# HW2.net
KiCad netlist of a schematic drawn in EAGLE
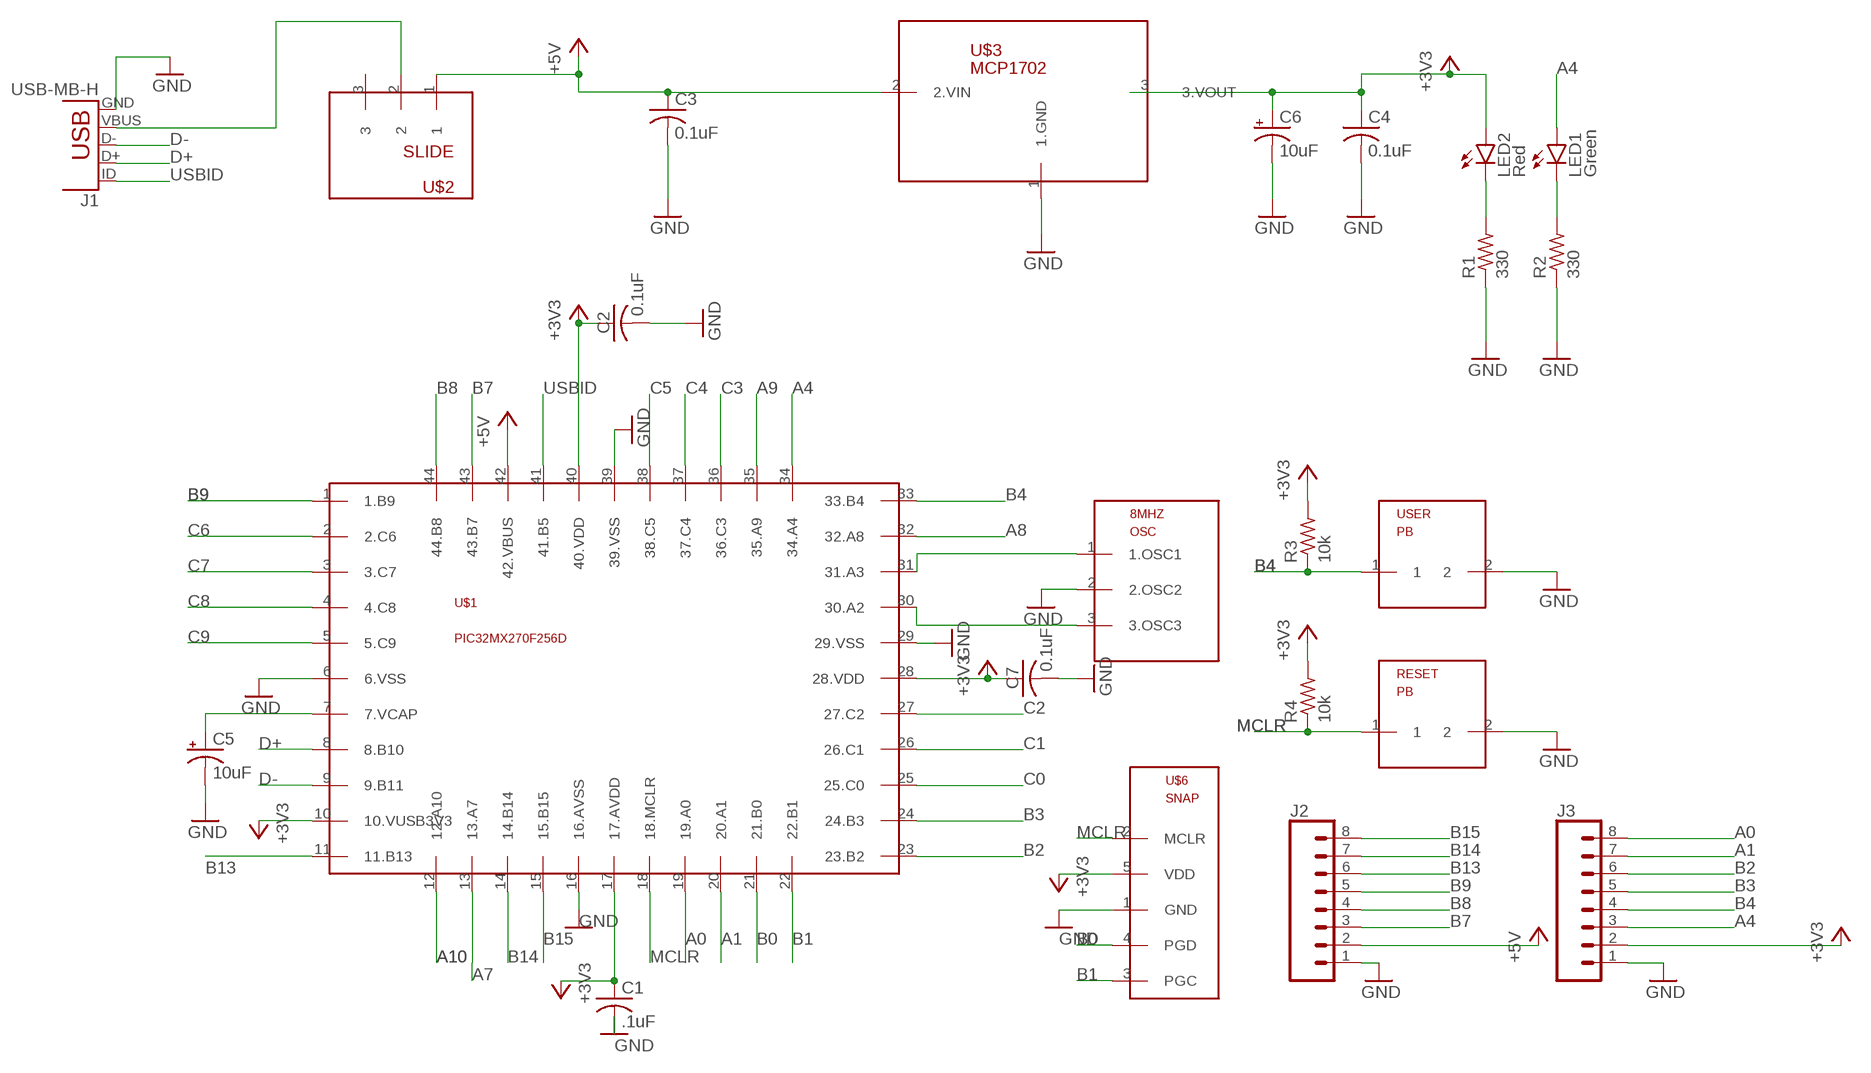
[diagram p0: schematic, sheet 1]

(export (version "E")
  (design (tool "Eeschema 10.0.6"))
  (components
    (comp (ref "8MHZ")
      (value "OSC")
      (footprint "eagle-import:OSC")
      (libsource (lib "eagle-import") (part "OSC"))
    )
    (comp (ref "C1")
      (value ".1uF")
      (footprint "eagle-import:C025-025X050")
      (libsource (lib "eagle-import") (part "C-US025-025X050"))
    )
    (comp (ref "C2")
      (value "0.1uF")
      (footprint "eagle-import:C025-025X050")
      (libsource (lib "eagle-import") (part "C-US025-025X050"))
    )
    (comp (ref "C3")
      (value "0.1uF")
      (footprint "eagle-import:C025-025X050")
      (libsource (lib "eagle-import") (part "C-US025-025X050"))
    )
    (comp (ref "C4")
      (value "0.1uF")
      (footprint "eagle-import:C025-025X050")
      (libsource (lib "eagle-import") (part "C-US025-025X050"))
    )
    (comp (ref "C5")
      (value "10uF")
      (footprint "eagle-import:B45181B")
      (libsource (lib "eagle-import") (part "CPOL-USB45181B"))
    )
    (comp (ref "C6")
      (value "10uF")
      (footprint "eagle-import:B45181B")
      (libsource (lib "eagle-import") (part "CPOL-USB45181B"))
    )
    (comp (ref "C7")
      (value "0.1uF")
      (footprint "eagle-import:C025-025X050")
      (libsource (lib "eagle-import") (part "C-US025-025X050"))
    )
    (comp (ref "J1")
      (value "USB-MB-H")
      (footprint "eagle-import:USB-MB-H")
      (libsource (lib "eagle-import") (part "USB-MB-H"))
    )
    (comp (ref "J2")
      (value "CONN_08")
      (footprint "eagle-import:CONN_08")
      (libsource (lib "eagle-import") (part "CONN_08"))
    )
    (comp (ref "J3")
      (value "CONN_08")
      (footprint "eagle-import:CONN_08")
      (libsource (lib "eagle-import") (part "CONN_08"))
    )
    (comp (ref "LED1")
      (value "Green")
      (footprint "eagle-import:LED3MM")
      (libsource (lib "eagle-import") (part "LED3MM"))
    )
    (comp (ref "LED2")
      (value "Red")
      (footprint "eagle-import:LED3MM")
      (libsource (lib "eagle-import") (part "LED3MM"))
    )
    (comp (ref "R1")
      (value "330")
      (footprint "eagle-import:0207_10")
      (libsource (lib "eagle-import") (part "R-US_0207/10"))
    )
    (comp (ref "R2")
      (value "330")
      (footprint "eagle-import:0207_10")
      (libsource (lib "eagle-import") (part "R-US_0207/10"))
    )
    (comp (ref "R3")
      (value "10k")
      (footprint "eagle-import:0207_10")
      (libsource (lib "eagle-import") (part "R-US_0207/10"))
    )
    (comp (ref "R4")
      (value "10k")
      (footprint "eagle-import:0207_10")
      (libsource (lib "eagle-import") (part "R-US_0207/10"))
    )
    (comp (ref "RESET")
      (value "PB")
      (footprint "eagle-import:PB")
      (libsource (lib "eagle-import") (part "PB"))
    )
    (comp (ref "U$1")
      (value "PIC32MX270F256D")
      (footprint "eagle-import:MQFP44-2")
      (libsource (lib "eagle-import") (part "PIC32MX270F256D"))
    )
    (comp (ref "U$2")
      (value "SLIDE")
      (footprint "eagle-import:SLIDE")
      (libsource (lib "eagle-import") (part "SLIDE"))
    )
    (comp (ref "U$3")
      (value "MCP1702")
      (footprint "eagle-import:TO92")
      (libsource (lib "eagle-import") (part "MCP1702"))
    )
    (comp (ref "U$6")
      (value "SNAP")
      (footprint "eagle-import:1X05")
      (libsource (lib "eagle-import") (part "SNAP"))
    )
    (comp (ref "USER")
      (value "PB")
      (footprint "eagle-import:PB")
      (libsource (lib "eagle-import") (part "PB"))
    )
  )
  (nets
    (net (code "1") (name "+3V3") (class "Default")
      (node (ref "C1") (pin "1") (pinfunction "1_1") (pintype "passive"))
      (node (ref "C2") (pin "1") (pinfunction "1_1") (pintype "passive"))
      (node (ref "C4") (pin "1") (pinfunction "1_1") (pintype "passive"))
      (node (ref "C6") (pin "+") (pinfunction "+_+") (pintype "passive"))
      (node (ref "C7") (pin "1") (pinfunction "1_1") (pintype "passive"))
      (node (ref "J3") (pin "2") (pinfunction "2_2") (pintype "passive"))
      (node (ref "LED2") (pin "A") (pinfunction "A_A") (pintype "passive"))
      (node (ref "R3") (pin "2") (pinfunction "2_2") (pintype "passive"))
      (node (ref "R4") (pin "2") (pinfunction "2_2") (pintype "passive"))
      (node (ref "U$1") (pin "10") (pinfunction "10.VUSB3V3_10") (pintype "bidirectional"))
      (node (ref "U$1") (pin "17") (pinfunction "17.AVDD_17") (pintype "bidirectional"))
      (node (ref "U$1") (pin "28") (pinfunction "28.VDD_28") (pintype "bidirectional"))
      (node (ref "U$1") (pin "40") (pinfunction "40.VDD_40") (pintype "bidirectional"))
      (node (ref "U$3") (pin "3") (pinfunction "3.VOUT_3") (pintype "bidirectional"))
      (node (ref "U$6") (pin "5") (pinfunction "VDD_5") (pintype "bidirectional"))
    )
    (net (code "2") (name "+5V") (class "Default")
      (node (ref "C3") (pin "1") (pinfunction "1_1") (pintype "passive"))
      (node (ref "J2") (pin "2") (pinfunction "2_2") (pintype "passive"))
      (node (ref "U$1") (pin "42") (pinfunction "42.VBUS_42") (pintype "bidirectional"))
      (node (ref "U$2") (pin "1") (pinfunction "1_1") (pintype "bidirectional"))
      (node (ref "U$3") (pin "2") (pinfunction "2.VIN_2") (pintype "bidirectional"))
    )
    (net (code "3") (name "/A0") (class "Default")
      (node (ref "J3") (pin "8") (pinfunction "8_8") (pintype "passive"))
      (node (ref "U$1") (pin "19") (pinfunction "19.A0_19") (pintype "bidirectional"))
    )
    (net (code "4") (name "/A1") (class "Default")
      (node (ref "J3") (pin "7") (pinfunction "7_7") (pintype "passive"))
      (node (ref "U$1") (pin "20") (pinfunction "20.A1_20") (pintype "bidirectional"))
    )
    (net (code "5") (name "/A4") (class "Default")
      (node (ref "J3") (pin "3") (pinfunction "3_3") (pintype "passive"))
      (node (ref "LED1") (pin "A") (pinfunction "A_A") (pintype "passive"))
      (node (ref "U$1") (pin "34") (pinfunction "34.A4_34") (pintype "bidirectional"))
    )
    (net (code "6") (name "/A7") (class "Default")
      (node (ref "U$1") (pin "13") (pinfunction "13.A7_13") (pintype "bidirectional"))
    )
    (net (code "7") (name "/A8") (class "Default")
      (node (ref "U$1") (pin "32") (pinfunction "32.A8_32") (pintype "bidirectional"))
    )
    (net (code "8") (name "/A9") (class "Default")
      (node (ref "U$1") (pin "35") (pinfunction "35.A9_35") (pintype "bidirectional"))
    )
    (net (code "9") (name "/A10") (class "Default")
      (node (ref "U$1") (pin "12") (pinfunction "12.A10_12") (pintype "bidirectional"))
    )
    (net (code "10") (name "/B0") (class "Default")
      (node (ref "U$1") (pin "21") (pinfunction "21.B0_21") (pintype "bidirectional"))
      (node (ref "U$6") (pin "4") (pinfunction "PGD_4") (pintype "bidirectional"))
    )
    (net (code "11") (name "/B1") (class "Default")
      (node (ref "U$1") (pin "22") (pinfunction "22.B1_22") (pintype "bidirectional"))
      (node (ref "U$6") (pin "3") (pinfunction "PGC_3") (pintype "bidirectional"))
    )
    (net (code "12") (name "/B2") (class "Default")
      (node (ref "J3") (pin "6") (pinfunction "6_6") (pintype "passive"))
      (node (ref "U$1") (pin "23") (pinfunction "23.B2_23") (pintype "bidirectional"))
    )
    (net (code "13") (name "/B3") (class "Default")
      (node (ref "J3") (pin "5") (pinfunction "5_5") (pintype "passive"))
      (node (ref "U$1") (pin "24") (pinfunction "24.B3_24") (pintype "bidirectional"))
    )
    (net (code "14") (name "/B4") (class "Default")
      (node (ref "J3") (pin "4") (pinfunction "4_4") (pintype "passive"))
      (node (ref "R3") (pin "1") (pinfunction "1_1") (pintype "passive"))
      (node (ref "U$1") (pin "33") (pinfunction "33.B4_33") (pintype "bidirectional"))
      (node (ref "USER") (pin "1") (pinfunction "1_1") (pintype "bidirectional"))
    )
    (net (code "15") (name "/B7") (class "Default")
      (node (ref "J2") (pin "3") (pinfunction "3_3") (pintype "passive"))
      (node (ref "U$1") (pin "43") (pinfunction "43.B7_43") (pintype "bidirectional"))
    )
    (net (code "16") (name "/B8") (class "Default")
      (node (ref "J2") (pin "4") (pinfunction "4_4") (pintype "passive"))
      (node (ref "U$1") (pin "44") (pinfunction "44.B8_44") (pintype "bidirectional"))
    )
    (net (code "17") (name "/B9") (class "Default")
      (node (ref "J2") (pin "5") (pinfunction "5_5") (pintype "passive"))
      (node (ref "U$1") (pin "1") (pinfunction "1.B9_1") (pintype "bidirectional"))
    )
    (net (code "18") (name "/B13") (class "Default")
      (node (ref "J2") (pin "6") (pinfunction "6_6") (pintype "passive"))
      (node (ref "U$1") (pin "11") (pinfunction "11.B13_11") (pintype "bidirectional"))
    )
    (net (code "19") (name "/B14") (class "Default")
      (node (ref "J2") (pin "7") (pinfunction "7_7") (pintype "passive"))
      (node (ref "U$1") (pin "14") (pinfunction "14.B14_14") (pintype "bidirectional"))
    )
    (net (code "20") (name "/B15") (class "Default")
      (node (ref "J2") (pin "8") (pinfunction "8_8") (pintype "passive"))
      (node (ref "U$1") (pin "15") (pinfunction "15.B15_15") (pintype "bidirectional"))
    )
    (net (code "21") (name "/C0") (class "Default")
      (node (ref "U$1") (pin "25") (pinfunction "25.C0_25") (pintype "bidirectional"))
    )
    (net (code "22") (name "/C1") (class "Default")
      (node (ref "U$1") (pin "26") (pinfunction "26.C1_26") (pintype "bidirectional"))
    )
    (net (code "23") (name "/C2") (class "Default")
      (node (ref "U$1") (pin "27") (pinfunction "27.C2_27") (pintype "bidirectional"))
    )
    (net (code "24") (name "/C3") (class "Default")
      (node (ref "U$1") (pin "36") (pinfunction "36.C3_36") (pintype "bidirectional"))
    )
    (net (code "25") (name "/C4") (class "Default")
      (node (ref "U$1") (pin "37") (pinfunction "37.C4_37") (pintype "bidirectional"))
    )
    (net (code "26") (name "/C5") (class "Default")
      (node (ref "U$1") (pin "38") (pinfunction "38.C5_38") (pintype "bidirectional"))
    )
    (net (code "27") (name "/C6") (class "Default")
      (node (ref "U$1") (pin "2") (pinfunction "2.C6_2") (pintype "bidirectional"))
    )
    (net (code "28") (name "/C7") (class "Default")
      (node (ref "U$1") (pin "3") (pinfunction "3.C7_3") (pintype "bidirectional"))
    )
    (net (code "29") (name "/C8") (class "Default")
      (node (ref "U$1") (pin "4") (pinfunction "4.C8_4") (pintype "bidirectional"))
    )
    (net (code "30") (name "/C9") (class "Default")
      (node (ref "U$1") (pin "5") (pinfunction "5.C9_5") (pintype "bidirectional"))
    )
    (net (code "31") (name "/D+") (class "Default")
      (node (ref "J1") (pin "D+") (pinfunction "D+_D+") (pintype "bidirectional"))
      (node (ref "U$1") (pin "8") (pinfunction "8.B10_8") (pintype "bidirectional"))
    )
    (net (code "32") (name "/D-") (class "Default")
      (node (ref "J1") (pin "D-") (pinfunction "D-_D-") (pintype "bidirectional"))
      (node (ref "U$1") (pin "9") (pinfunction "9.B11_9") (pintype "bidirectional"))
    )
    (net (code "33") (name "/MCLR") (class "Default")
      (node (ref "R4") (pin "1") (pinfunction "1_1") (pintype "passive"))
      (node (ref "RESET") (pin "1") (pinfunction "1_1") (pintype "bidirectional"))
      (node (ref "U$1") (pin "18") (pinfunction "18.MCLR_18") (pintype "bidirectional"))
      (node (ref "U$6") (pin "2") (pinfunction "MCLR_2") (pintype "bidirectional"))
    )
    (net (code "34") (name "/USBID") (class "Default")
      (node (ref "J1") (pin "ID") (pinfunction "ID_ID") (pintype "bidirectional"))
      (node (ref "U$1") (pin "41") (pinfunction "41.B5_41") (pintype "bidirectional"))
    )
    (net (code "35") (name "GND") (class "Default")
      (node (ref "8MHZ") (pin "2") (pinfunction "2.OSC2_2") (pintype "bidirectional"))
      (node (ref "C1") (pin "2") (pinfunction "2_2") (pintype "passive"))
      (node (ref "C2") (pin "2") (pinfunction "2_2") (pintype "passive"))
      (node (ref "C3") (pin "2") (pinfunction "2_2") (pintype "passive"))
      (node (ref "C4") (pin "2") (pinfunction "2_2") (pintype "passive"))
      (node (ref "C5") (pin "-") (pinfunction "-_-") (pintype "passive"))
      (node (ref "C6") (pin "-") (pinfunction "-_-") (pintype "passive"))
      (node (ref "C7") (pin "2") (pinfunction "2_2") (pintype "passive"))
      (node (ref "J1") (pin "GND") (pinfunction "GND_GND") (pintype "bidirectional"))
      (node (ref "J2") (pin "1") (pinfunction "1_1") (pintype "passive"))
      (node (ref "J3") (pin "1") (pinfunction "1_1") (pintype "passive"))
      (node (ref "R1") (pin "1") (pinfunction "1_1") (pintype "passive"))
      (node (ref "R2") (pin "1") (pinfunction "1_1") (pintype "passive"))
      (node (ref "RESET") (pin "2") (pinfunction "2_2") (pintype "bidirectional"))
      (node (ref "U$1") (pin "16") (pinfunction "16.AVSS_16") (pintype "bidirectional"))
      (node (ref "U$1") (pin "29") (pinfunction "29.VSS_29") (pintype "bidirectional"))
      (node (ref "U$1") (pin "39") (pinfunction "39.VSS_39") (pintype "bidirectional"))
      (node (ref "U$1") (pin "6") (pinfunction "6.VSS_6") (pintype "bidirectional"))
      (node (ref "U$3") (pin "1") (pinfunction "1.GND_1") (pintype "bidirectional"))
      (node (ref "U$6") (pin "1") (pinfunction "GND_1") (pintype "bidirectional"))
      (node (ref "USER") (pin "2") (pinfunction "2_2") (pintype "bidirectional"))
    )
    (net (code "36") (name "Net-(8MHZ-1.OSC1)") (class "Default")
      (node (ref "8MHZ") (pin "1") (pinfunction "1.OSC1_1") (pintype "bidirectional"))
      (node (ref "U$1") (pin "31") (pinfunction "31.A3_31") (pintype "bidirectional"))
    )
    (net (code "37") (name "Net-(8MHZ-3.OSC3)") (class "Default")
      (node (ref "8MHZ") (pin "3") (pinfunction "3.OSC3_3") (pintype "bidirectional"))
      (node (ref "U$1") (pin "30") (pinfunction "30.A2_30") (pintype "bidirectional"))
    )
    (net (code "38") (name "Net-(J1-PadVBUS)") (class "Default")
      (node (ref "J1") (pin "VBUS") (pinfunction "VBUS_VBUS") (pintype "bidirectional"))
      (node (ref "U$2") (pin "2") (pinfunction "2_2") (pintype "bidirectional"))
    )
    (net (code "39") (name "Net-(LED1-C)") (class "Default")
      (node (ref "LED1") (pin "K") (pinfunction "C_K") (pintype "passive"))
      (node (ref "R2") (pin "2") (pinfunction "2_2") (pintype "passive"))
    )
    (net (code "40") (name "Net-(LED2-C)") (class "Default")
      (node (ref "LED2") (pin "K") (pinfunction "C_K") (pintype "passive"))
      (node (ref "R1") (pin "2") (pinfunction "2_2") (pintype "passive"))
    )
    (net (code "41") (name "Net-(U$1-7.VCAP)") (class "Default")
      (node (ref "C5") (pin "+") (pinfunction "+_+") (pintype "passive"))
      (node (ref "U$1") (pin "7") (pinfunction "7.VCAP_7") (pintype "bidirectional"))
    )
    (net (code "42") (name "unconnected-(U$2-Pad3)") (class "Default")
      (node (ref "U$2") (pin "3") (pinfunction "3_3") (pintype "bidirectional"))
    )
  )
)
